# mouse_v1.net
KiCad netlist of a schematic drawn in EAGLE
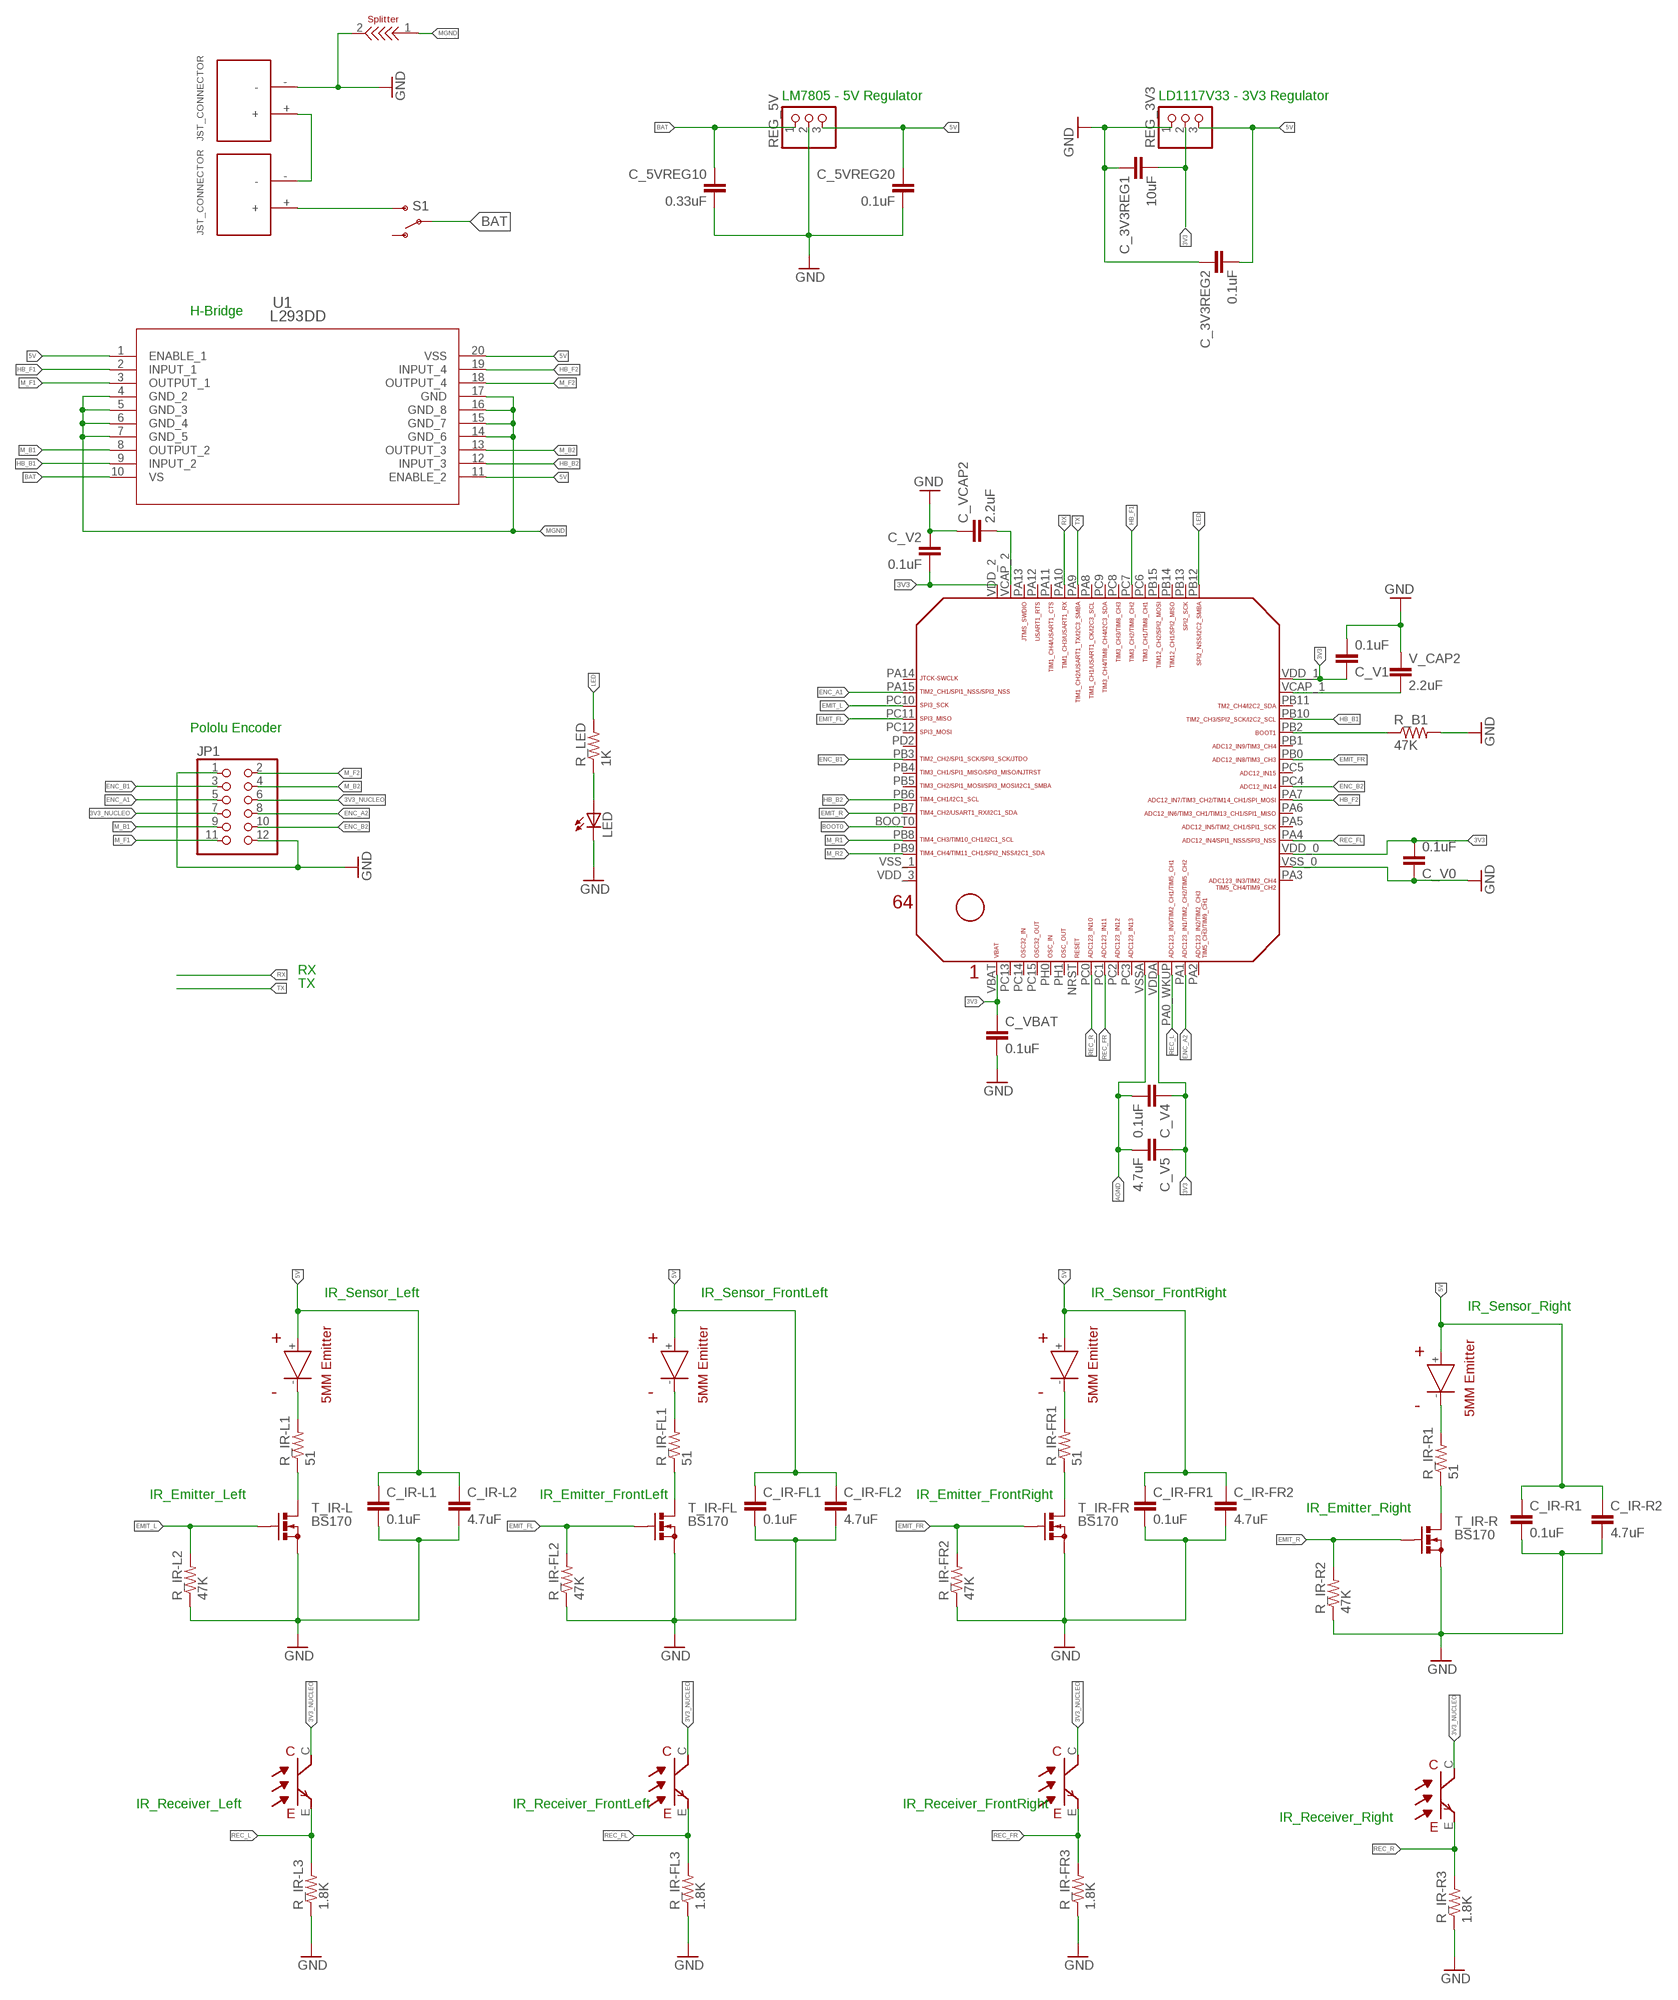
[diagram p0: schematic, sheet 1]

(export (version "E")
  (design (tool "Eeschema 10.0.6"))
  (components
    (comp (ref "C_3V3REG1")
      (value "10uF")
      (footprint "eagle-import:0603-CAP")
      (libsource (lib "eagle-import") (part "CAP0603-CAP"))
    )
    (comp (ref "C_3V3REG2")
      (value "0.1uF")
      (footprint "eagle-import:0603-CAP")
      (libsource (lib "eagle-import") (part "CAP0603-CAP"))
    )
    (comp (ref "C_5VREG10")
      (value "0.33uF")
      (footprint "eagle-import:0603-CAP")
      (libsource (lib "eagle-import") (part "CAP0603-CAP"))
    )
    (comp (ref "C_5VREG20")
      (value "0.1uF")
      (footprint "eagle-import:0603-CAP")
      (libsource (lib "eagle-import") (part "CAP0603-CAP"))
    )
    (comp (ref "C_IR-FL1")
      (value "0.1uF")
      (footprint "eagle-import:0603-CAP")
      (libsource (lib "eagle-import") (part "CAP0603-CAP"))
    )
    (comp (ref "C_IR-FL2")
      (value "4.7uF")
      (footprint "eagle-import:0603-CAP")
      (libsource (lib "eagle-import") (part "CAP0603-CAP"))
    )
    (comp (ref "C_IR-FR1")
      (value "0.1uF")
      (footprint "eagle-import:0603-CAP")
      (libsource (lib "eagle-import") (part "CAP0603-CAP"))
    )
    (comp (ref "C_IR-FR2")
      (value "4.7uF")
      (footprint "eagle-import:0603-CAP")
      (libsource (lib "eagle-import") (part "CAP0603-CAP"))
    )
    (comp (ref "C_IR-L1")
      (value "0.1uF")
      (footprint "eagle-import:0603-CAP")
      (libsource (lib "eagle-import") (part "CAP0603-CAP"))
    )
    (comp (ref "C_IR-L2")
      (value "4.7uF")
      (footprint "eagle-import:0603-CAP")
      (libsource (lib "eagle-import") (part "CAP0603-CAP"))
    )
    (comp (ref "C_IR-R1")
      (value "0.1uF")
      (footprint "eagle-import:0603-CAP")
      (libsource (lib "eagle-import") (part "CAP0603-CAP"))
    )
    (comp (ref "C_IR-R2")
      (value "4.7uF")
      (footprint "eagle-import:0603-CAP")
      (libsource (lib "eagle-import") (part "CAP0603-CAP"))
    )
    (comp (ref "C_V0")
      (value "0.1uF")
      (footprint "eagle-import:0603-CAP")
      (libsource (lib "eagle-import") (part "CAP0603-CAP"))
    )
    (comp (ref "C_V1")
      (value "0.1uF")
      (footprint "eagle-import:0603-CAP")
      (libsource (lib "eagle-import") (part "CAP0603-CAP"))
    )
    (comp (ref "C_V2")
      (value "0.1uF")
      (footprint "eagle-import:0603-CAP")
      (libsource (lib "eagle-import") (part "CAP0603-CAP"))
    )
    (comp (ref "C_V4")
      (value "0.1uF")
      (footprint "eagle-import:0603-CAP")
      (libsource (lib "eagle-import") (part "CAP0603-CAP"))
    )
    (comp (ref "C_V5")
      (value "4.7uF")
      (footprint "eagle-import:0603-CAP")
      (libsource (lib "eagle-import") (part "CAP0603-CAP"))
    )
    (comp (ref "C_VBAT")
      (value "0.1uF")
      (footprint "eagle-import:0603-CAP")
      (libsource (lib "eagle-import") (part "CAP0603-CAP"))
    )
    (comp (ref "C_VCAP2")
      (value "2.2uF")
      (footprint "eagle-import:0603-CAP")
      (libsource (lib "eagle-import") (part "CAP0603-CAP"))
    )
    (comp (ref "IR_FL")
      (value "EMITTER")
      (footprint "eagle-import:EMITTER")
      (libsource (lib "eagle-import") (part "EMITTER"))
    )
    (comp (ref "IR_FR")
      (value "EMITTER")
      (footprint "eagle-import:EMITTER")
      (libsource (lib "eagle-import") (part "EMITTER"))
    )
    (comp (ref "IR_L")
      (value "EMITTER")
      (footprint "eagle-import:EMITTER")
      (libsource (lib "eagle-import") (part "EMITTER"))
    )
    (comp (ref "IR_R")
      (value "EMITTER")
      (footprint "eagle-import:EMITTER")
      (libsource (lib "eagle-import") (part "EMITTER"))
    )
    (comp (ref "JP1")
      (value "PINHD-2X6")
      (footprint "eagle-import:2X06")
      (libsource (lib "eagle-import") (part "PINHD-2X6"))
    )
    (comp (ref "LED")
      (value "LEDCHIPLED_0603")
      (footprint "eagle-import:CHIPLED_0603")
      (libsource (lib "eagle-import") (part "LEDCHIPLED_0603"))
    )
    (comp (ref "REG_3V3")
      (value "PINHD-1X3")
      (footprint "eagle-import:1X03")
      (libsource (lib "eagle-import") (part "PINHD-1X3"))
    )
    (comp (ref "REG_5V")
      (value "PINHD-1X3")
      (footprint "eagle-import:1X03")
      (libsource (lib "eagle-import") (part "PINHD-1X3"))
    )
    (comp (ref "R_B1")
      (value "47K")
      (footprint "eagle-import:0603-RES")
      (libsource (lib "eagle-import") (part "1.8KOHM1/10W1%(0603)"))
    )
    (comp (ref "R_IR-FL1")
      (value "51")
      (footprint "eagle-import:0603-RES")
      (libsource (lib "eagle-import") (part "1.8KOHM1/10W1%(0603)"))
    )
    (comp (ref "R_IR-FL2")
      (value "47K")
      (footprint "eagle-import:0603-RES")
      (libsource (lib "eagle-import") (part "1.8KOHM1/10W1%(0603)"))
    )
    (comp (ref "R_IR-FL3")
      (value "1.8K")
      (footprint "eagle-import:0603-RES")
      (libsource (lib "eagle-import") (part "1.8KOHM1/10W1%(0603)"))
    )
    (comp (ref "R_IR-FR1")
      (value "51")
      (footprint "eagle-import:0603-RES")
      (libsource (lib "eagle-import") (part "1.8KOHM1/10W1%(0603)"))
    )
    (comp (ref "R_IR-FR2")
      (value "47K")
      (footprint "eagle-import:0603-RES")
      (libsource (lib "eagle-import") (part "1.8KOHM1/10W1%(0603)"))
    )
    (comp (ref "R_IR-FR3")
      (value "1.8K")
      (footprint "eagle-import:0603-RES")
      (libsource (lib "eagle-import") (part "1.8KOHM1/10W1%(0603)"))
    )
    (comp (ref "R_IR-L1")
      (value "51")
      (footprint "eagle-import:0603-RES")
      (libsource (lib "eagle-import") (part "1.8KOHM1/10W1%(0603)"))
    )
    (comp (ref "R_IR-L2")
      (value "47K")
      (footprint "eagle-import:0603-RES")
      (libsource (lib "eagle-import") (part "1.8KOHM1/10W1%(0603)"))
    )
    (comp (ref "R_IR-L3")
      (value "1.8K")
      (footprint "eagle-import:0603-RES")
      (libsource (lib "eagle-import") (part "1.8KOHM1/10W1%(0603)"))
    )
    (comp (ref "R_IR-R1")
      (value "51")
      (footprint "eagle-import:0603-RES")
      (libsource (lib "eagle-import") (part "1.8KOHM1/10W1%(0603)"))
    )
    (comp (ref "R_IR-R2")
      (value "47K")
      (footprint "eagle-import:0603-RES")
      (libsource (lib "eagle-import") (part "1.8KOHM1/10W1%(0603)"))
    )
    (comp (ref "R_IR-R3")
      (value "1.8K")
      (footprint "eagle-import:0603-RES")
      (libsource (lib "eagle-import") (part "1.8KOHM1/10W1%(0603)"))
    )
    (comp (ref "R_LED")
      (value "1K")
      (footprint "eagle-import:0603-RES")
      (libsource (lib "eagle-import") (part "1.8KOHM1/10W1%(0603)"))
    )
    (comp (ref "S1")
      (value "SWITCH-SPSTKIT")
      (footprint "eagle-import:SWITCH-SPDT_KIT")
      (libsource (lib "eagle-import") (part "SWITCH-SPSTKIT"))
    )
    (comp (ref "T_IR-FL")
      (value "BS170")
      (footprint "eagle-import:SOT54E")
      (libsource (lib "eagle-import") (part "BS170"))
    )
    (comp (ref "T_IR-FR")
      (value "BS170")
      (footprint "eagle-import:SOT54E")
      (libsource (lib "eagle-import") (part "BS170"))
    )
    (comp (ref "T_IR-L")
      (value "BS170")
      (footprint "eagle-import:SOT54E")
      (libsource (lib "eagle-import") (part "BS170"))
    )
    (comp (ref "T_IR-R")
      (value "BS170")
      (footprint "eagle-import:SOT54E")
      (libsource (lib "eagle-import") (part "BS170"))
    )
    (comp (ref "U$1")
      (value "STM32F405/415_LQFP64")
      (footprint "eagle-import:STM32F405_415_LQFP64")
      (libsource (lib "eagle-import") (part "STM32F405/415_LQFP64"))
    )
    (comp (ref "U$2")
      (value "JST_CONNECTOR_FEMALE")
      (footprint "eagle-import:JST_CONNECTOR_FEMALE")
      (libsource (lib "eagle-import") (part "JST_CONNECTOR_FEMALE"))
    )
    (comp (ref "U$3")
      (value "JST_CONNECTOR_FEMALE")
      (footprint "eagle-import:JST_CONNECTOR_FEMALE")
      (libsource (lib "eagle-import") (part "JST_CONNECTOR_FEMALE"))
    )
    (comp (ref "U$4")
      (value "RECEIVER")
      (footprint "eagle-import:RECEIVER")
      (libsource (lib "eagle-import") (part "RECEIVER"))
    )
    (comp (ref "U$5")
      (value "RECEIVER")
      (footprint "eagle-import:RECEIVER")
      (libsource (lib "eagle-import") (part "RECEIVER"))
    )
    (comp (ref "U$6")
      (value "RECEIVER")
      (footprint "eagle-import:RECEIVER")
      (libsource (lib "eagle-import") (part "RECEIVER"))
    )
    (comp (ref "U$7")
      (value "RECEIVER")
      (footprint "eagle-import:RECEIVER")
      (libsource (lib "eagle-import") (part "RECEIVER"))
    )
    (comp (ref "U$8")
      (value "SPLITTER")
      (footprint "eagle-import:SPLITTER")
      (libsource (lib "eagle-import") (part "SPLITTER"))
    )
    (comp (ref "U1")
      (value "L293DD")
      (footprint "eagle-import:SO-20")
      (libsource (lib "eagle-import") (part "L293DD"))
    )
    (comp (ref "V_CAP2")
      (value "2.2uF")
      (footprint "eagle-import:0603-CAP")
      (libsource (lib "eagle-import") (part "CAP0603-CAP"))
    )
  )
  (nets
    (net (code "1") (name "3V3") (class "Default")
      (node (ref "C_3V3REG1") (pin "2") (pinfunction "2_2") (pintype "passive"))
      (node (ref "C_V0") (pin "2") (pinfunction "2_2") (pintype "passive"))
      (node (ref "C_V1") (pin "1") (pinfunction "1_1") (pintype "passive"))
      (node (ref "C_V2") (pin "2") (pinfunction "2_2") (pintype "passive"))
      (node (ref "C_V4") (pin "1") (pinfunction "1_1") (pintype "passive"))
      (node (ref "C_V5") (pin "1") (pinfunction "1_1") (pintype "passive"))
      (node (ref "C_VBAT") (pin "1") (pinfunction "1_1") (pintype "passive"))
      (node (ref "REG_3V3") (pin "2") (pinfunction "2_2") (pintype "passive"))
      (node (ref "U$1") (pin "VBAT") (pinfunction "VBAT_VBAT") (pintype "bidirectional"))
      (node (ref "U$1") (pin "VDDA") (pinfunction "VDDA_VDDA") (pintype "bidirectional"))
      (node (ref "U$1") (pin "VDD_0") (pinfunction "VDD_0_VDD_0") (pintype "bidirectional"))
      (node (ref "U$1") (pin "VDD_1") (pinfunction "VDD_1_VDD_1") (pintype "bidirectional"))
      (node (ref "U$1") (pin "VDD_2") (pinfunction "VDD_2_VDD_2") (pintype "bidirectional"))
    )
    (net (code "2") (name "3V3_NUCLEO") (class "Default")
      (node (ref "JP1") (pin "6") (pinfunction "6_6") (pintype "passive"))
      (node (ref "JP1") (pin "7") (pinfunction "7_7") (pintype "passive"))
      (node (ref "U$4") (pin "C") (pinfunction "C_C") (pintype "bidirectional"))
      (node (ref "U$5") (pin "C") (pinfunction "C_C") (pintype "bidirectional"))
      (node (ref "U$6") (pin "C") (pinfunction "C_C") (pintype "bidirectional"))
      (node (ref "U$7") (pin "C") (pinfunction "C_C") (pintype "bidirectional"))
    )
    (net (code "3") (name "5V") (class "Default")
      (node (ref "C_3V3REG2") (pin "2") (pinfunction "2_2") (pintype "passive"))
      (node (ref "C_5VREG20") (pin "1") (pinfunction "1_1") (pintype "passive"))
      (node (ref "C_IR-FL1") (pin "1") (pinfunction "1_1") (pintype "passive"))
      (node (ref "C_IR-FL2") (pin "1") (pinfunction "1_1") (pintype "passive"))
      (node (ref "C_IR-FR1") (pin "1") (pinfunction "1_1") (pintype "passive"))
      (node (ref "C_IR-FR2") (pin "1") (pinfunction "1_1") (pintype "passive"))
      (node (ref "C_IR-L1") (pin "1") (pinfunction "1_1") (pintype "passive"))
      (node (ref "C_IR-L2") (pin "1") (pinfunction "1_1") (pintype "passive"))
      (node (ref "C_IR-R1") (pin "1") (pinfunction "1_1") (pintype "passive"))
      (node (ref "C_IR-R2") (pin "1") (pinfunction "1_1") (pintype "passive"))
      (node (ref "IR_FL") (pin "+") (pinfunction "+_+") (pintype "bidirectional"))
      (node (ref "IR_FR") (pin "+") (pinfunction "+_+") (pintype "bidirectional"))
      (node (ref "IR_L") (pin "+") (pinfunction "+_+") (pintype "bidirectional"))
      (node (ref "IR_R") (pin "+") (pinfunction "+_+") (pintype "bidirectional"))
      (node (ref "REG_3V3") (pin "3") (pinfunction "3_3") (pintype "passive"))
      (node (ref "REG_5V") (pin "3") (pinfunction "3_3") (pintype "passive"))
      (node (ref "U1") (pin "1") (pinfunction "ENABLE_1_1") (pintype "input"))
      (node (ref "U1") (pin "11") (pinfunction "ENABLE_2_11") (pintype "input"))
      (node (ref "U1") (pin "20") (pinfunction "VSS_20") (pintype "passive"))
    )
    (net (code "4") (name "AGND") (class "Default")
      (node (ref "C_V4") (pin "2") (pinfunction "2_2") (pintype "passive"))
      (node (ref "C_V5") (pin "2") (pinfunction "2_2") (pintype "passive"))
      (node (ref "U$1") (pin "VSSA") (pinfunction "VSSA_VSSA") (pintype "bidirectional"))
    )
    (net (code "5") (name "BAT") (class "Default")
      (node (ref "C_5VREG10") (pin "1") (pinfunction "1_1") (pintype "passive"))
      (node (ref "REG_5V") (pin "1") (pinfunction "1_1") (pintype "passive"))
      (node (ref "S1") (pin "2") (pinfunction "P_2") (pintype "passive"))
      (node (ref "U1") (pin "10") (pinfunction "VS_10") (pintype "passive"))
    )
    (net (code "6") (name "BOOT0") (class "Default")
      (node (ref "U$1") (pin "BOOT0") (pinfunction "BOOT0_BOOT0") (pintype "bidirectional"))
    )
    (net (code "7") (name "EMIT_FL") (class "Default")
      (node (ref "R_IR-FL2") (pin "2") (pinfunction "2_2") (pintype "passive"))
      (node (ref "T_IR-FL") (pin "G") (pinfunction "G_G") (pintype "passive"))
      (node (ref "U$1") (pin "PC11") (pinfunction "PC11_PC11") (pintype "bidirectional"))
    )
    (net (code "8") (name "EMIT_FR") (class "Default")
      (node (ref "R_IR-FR2") (pin "2") (pinfunction "2_2") (pintype "passive"))
      (node (ref "T_IR-FR") (pin "G") (pinfunction "G_G") (pintype "passive"))
      (node (ref "U$1") (pin "PB0") (pinfunction "PB0_PB0") (pintype "bidirectional"))
    )
    (net (code "9") (name "EMIT_L") (class "Default")
      (node (ref "R_IR-L2") (pin "2") (pinfunction "2_2") (pintype "passive"))
      (node (ref "T_IR-L") (pin "G") (pinfunction "G_G") (pintype "passive"))
      (node (ref "U$1") (pin "PC10") (pinfunction "PC10_PC10") (pintype "bidirectional"))
    )
    (net (code "10") (name "EMIT_R") (class "Default")
      (node (ref "R_IR-R2") (pin "2") (pinfunction "2_2") (pintype "passive"))
      (node (ref "T_IR-R") (pin "G") (pinfunction "G_G") (pintype "passive"))
      (node (ref "U$1") (pin "PB7") (pinfunction "PB7_PB7") (pintype "bidirectional"))
    )
    (net (code "11") (name "ENC_A1") (class "Default")
      (node (ref "JP1") (pin "5") (pinfunction "5_5") (pintype "passive"))
      (node (ref "U$1") (pin "PA15") (pinfunction "PA15_PA15") (pintype "bidirectional"))
    )
    (net (code "12") (name "ENC_A2") (class "Default")
      (node (ref "JP1") (pin "8") (pinfunction "8_8") (pintype "passive"))
      (node (ref "U$1") (pin "PA1") (pinfunction "PA1_PA1") (pintype "bidirectional"))
    )
    (net (code "13") (name "ENC_B1") (class "Default")
      (node (ref "JP1") (pin "3") (pinfunction "3_3") (pintype "passive"))
      (node (ref "U$1") (pin "PB3") (pinfunction "PB3_PB3") (pintype "bidirectional"))
    )
    (net (code "14") (name "ENC_B2") (class "Default")
      (node (ref "JP1") (pin "10") (pinfunction "10_10") (pintype "passive"))
      (node (ref "U$1") (pin "PC4") (pinfunction "PC4_PC4") (pintype "bidirectional"))
    )
    (net (code "15") (name "GND") (class "Default")
      (node (ref "C_3V3REG1") (pin "1") (pinfunction "1_1") (pintype "passive"))
      (node (ref "C_3V3REG2") (pin "1") (pinfunction "1_1") (pintype "passive"))
      (node (ref "C_5VREG10") (pin "2") (pinfunction "2_2") (pintype "passive"))
      (node (ref "C_5VREG20") (pin "2") (pinfunction "2_2") (pintype "passive"))
      (node (ref "C_IR-FL1") (pin "2") (pinfunction "2_2") (pintype "passive"))
      (node (ref "C_IR-FL2") (pin "2") (pinfunction "2_2") (pintype "passive"))
      (node (ref "C_IR-FR1") (pin "2") (pinfunction "2_2") (pintype "passive"))
      (node (ref "C_IR-FR2") (pin "2") (pinfunction "2_2") (pintype "passive"))
      (node (ref "C_IR-L1") (pin "2") (pinfunction "2_2") (pintype "passive"))
      (node (ref "C_IR-L2") (pin "2") (pinfunction "2_2") (pintype "passive"))
      (node (ref "C_IR-R1") (pin "2") (pinfunction "2_2") (pintype "passive"))
      (node (ref "C_IR-R2") (pin "2") (pinfunction "2_2") (pintype "passive"))
      (node (ref "C_V0") (pin "1") (pinfunction "1_1") (pintype "passive"))
      (node (ref "C_V1") (pin "2") (pinfunction "2_2") (pintype "passive"))
      (node (ref "C_V2") (pin "1") (pinfunction "1_1") (pintype "passive"))
      (node (ref "C_VBAT") (pin "2") (pinfunction "2_2") (pintype "passive"))
      (node (ref "C_VCAP2") (pin "1") (pinfunction "1_1") (pintype "passive"))
      (node (ref "JP1") (pin "1") (pinfunction "1_1") (pintype "passive"))
      (node (ref "JP1") (pin "12") (pinfunction "12_12") (pintype "passive"))
      (node (ref "LED") (pin "C") (pinfunction "C_C") (pintype "passive"))
      (node (ref "REG_3V3") (pin "1") (pinfunction "1_1") (pintype "passive"))
      (node (ref "REG_5V") (pin "2") (pinfunction "2_2") (pintype "passive"))
      (node (ref "R_B1") (pin "2") (pinfunction "2_2") (pintype "passive"))
      (node (ref "R_IR-FL2") (pin "1") (pinfunction "1_1") (pintype "passive"))
      (node (ref "R_IR-FL3") (pin "1") (pinfunction "1_1") (pintype "passive"))
      (node (ref "R_IR-FR2") (pin "1") (pinfunction "1_1") (pintype "passive"))
      (node (ref "R_IR-FR3") (pin "1") (pinfunction "1_1") (pintype "passive"))
      (node (ref "R_IR-L2") (pin "1") (pinfunction "1_1") (pintype "passive"))
      (node (ref "R_IR-L3") (pin "1") (pinfunction "1_1") (pintype "passive"))
      (node (ref "R_IR-R2") (pin "1") (pinfunction "1_1") (pintype "passive"))
      (node (ref "R_IR-R3") (pin "1") (pinfunction "1_1") (pintype "passive"))
      (node (ref "T_IR-FL") (pin "S") (pinfunction "S_S") (pintype "passive"))
      (node (ref "T_IR-FR") (pin "S") (pinfunction "S_S") (pintype "passive"))
      (node (ref "T_IR-L") (pin "S") (pinfunction "S_S") (pintype "passive"))
      (node (ref "T_IR-R") (pin "S") (pinfunction "S_S") (pintype "passive"))
      (node (ref "U$1") (pin "VSS_0") (pinfunction "VSS_0_VSS_0") (pintype "bidirectional"))
      (node (ref "U$2") (pin "-") (pinfunction "-_-") (pintype "bidirectional"))
      (node (ref "U$8") (pin "2") (pinfunction "2_2") (pintype "bidirectional"))
      (node (ref "V_CAP2") (pin "1") (pinfunction "1_1") (pintype "passive"))
    )
    (net (code "16") (name "HB_B1") (class "Default")
      (node (ref "U$1") (pin "PB10") (pinfunction "PB10_PB10") (pintype "bidirectional"))
      (node (ref "U1") (pin "9") (pinfunction "INPUT_2_9") (pintype "input"))
    )
    (net (code "17") (name "HB_B2") (class "Default")
      (node (ref "U$1") (pin "PB6") (pinfunction "PB6_PB6") (pintype "bidirectional"))
      (node (ref "U1") (pin "12") (pinfunction "INPUT_3_12") (pintype "input"))
    )
    (net (code "18") (name "HB_F1") (class "Default")
      (node (ref "U$1") (pin "PC7") (pinfunction "PC7_PC7") (pintype "bidirectional"))
      (node (ref "U1") (pin "2") (pinfunction "INPUT_1_2") (pintype "input"))
    )
    (net (code "19") (name "HB_F2") (class "Default")
      (node (ref "U$1") (pin "PA7") (pinfunction "PA7_PA7") (pintype "bidirectional"))
      (node (ref "U1") (pin "19") (pinfunction "INPUT_4_19") (pintype "input"))
    )
    (net (code "20") (name "LED") (class "Default")
      (node (ref "R_LED") (pin "2") (pinfunction "2_2") (pintype "passive"))
      (node (ref "U$1") (pin "PB12") (pinfunction "PB12_PB12") (pintype "bidirectional"))
    )
    (net (code "21") (name "MGND") (class "Default")
      (node (ref "U$8") (pin "1") (pinfunction "1_1") (pintype "bidirectional"))
      (node (ref "U1") (pin "14") (pinfunction "GND_6_14") (pintype "passive"))
      (node (ref "U1") (pin "15") (pinfunction "GND_7_15") (pintype "passive"))
      (node (ref "U1") (pin "16") (pinfunction "GND_8_16") (pintype "passive"))
      (node (ref "U1") (pin "17") (pinfunction "GND_17") (pintype "passive"))
      (node (ref "U1") (pin "4") (pinfunction "GND_2_4") (pintype "passive"))
      (node (ref "U1") (pin "5") (pinfunction "GND_3_5") (pintype "passive"))
      (node (ref "U1") (pin "6") (pinfunction "GND_4_6") (pintype "passive"))
      (node (ref "U1") (pin "7") (pinfunction "GND_5_7") (pintype "passive"))
    )
    (net (code "22") (name "M_B1") (class "Default")
      (node (ref "JP1") (pin "9") (pinfunction "9_9") (pintype "passive"))
      (node (ref "U1") (pin "8") (pinfunction "OUTPUT_2_8") (pintype "output"))
    )
    (net (code "23") (name "M_B2") (class "Default")
      (node (ref "JP1") (pin "4") (pinfunction "4_4") (pintype "passive"))
      (node (ref "U1") (pin "13") (pinfunction "OUTPUT_3_13") (pintype "output"))
    )
    (net (code "24") (name "M_F1") (class "Default")
      (node (ref "JP1") (pin "11") (pinfunction "11_11") (pintype "passive"))
      (node (ref "U1") (pin "3") (pinfunction "OUTPUT_1_3") (pintype "output"))
    )
    (net (code "25") (name "M_F2") (class "Default")
      (node (ref "JP1") (pin "2") (pinfunction "2_2") (pintype "passive"))
      (node (ref "U1") (pin "18") (pinfunction "OUTPUT_4_18") (pintype "output"))
    )
    (net (code "26") (name "M_R1") (class "Default")
      (node (ref "U$1") (pin "PB8") (pinfunction "PB8_PB8") (pintype "bidirectional"))
    )
    (net (code "27") (name "M_R2") (class "Default")
      (node (ref "U$1") (pin "PB9") (pinfunction "PB9_PB9") (pintype "bidirectional"))
    )
    (net (code "28") (name "Net-(C_VCAP2-Pad2)") (class "Default")
      (node (ref "C_VCAP2") (pin "2") (pinfunction "2_2") (pintype "passive"))
      (node (ref "U$1") (pin "VCAP_2") (pinfunction "VCAP_2_VCAP_2") (pintype "bidirectional"))
    )
    (net (code "29") (name "Net-(IR_FL-Pad-)") (class "Default")
      (node (ref "IR_FL") (pin "-") (pinfunction "-_-") (pintype "bidirectional"))
      (node (ref "R_IR-FL1") (pin "2") (pinfunction "2_2") (pintype "passive"))
    )
    (net (code "30") (name "Net-(IR_FR-Pad-)") (class "Default")
      (node (ref "IR_FR") (pin "-") (pinfunction "-_-") (pintype "bidirectional"))
      (node (ref "R_IR-FR1") (pin "2") (pinfunction "2_2") (pintype "passive"))
    )
    (net (code "31") (name "Net-(IR_L-Pad-)") (class "Default")
      (node (ref "IR_L") (pin "-") (pinfunction "-_-") (pintype "bidirectional"))
      (node (ref "R_IR-L1") (pin "2") (pinfunction "2_2") (pintype "passive"))
    )
    (net (code "32") (name "Net-(IR_R-Pad-)") (class "Default")
      (node (ref "IR_R") (pin "-") (pinfunction "-_-") (pintype "bidirectional"))
      (node (ref "R_IR-R1") (pin "2") (pinfunction "2_2") (pintype "passive"))
    )
    (net (code "33") (name "Net-(LED-PadA)") (class "Default")
      (node (ref "LED") (pin "A") (pinfunction "A_A") (pintype "passive"))
      (node (ref "R_LED") (pin "1") (pinfunction "1_1") (pintype "passive"))
    )
    (net (code "34") (name "Net-(R_B1-Pad1)") (class "Default")
      (node (ref "R_B1") (pin "1") (pinfunction "1_1") (pintype "passive"))
      (node (ref "U$1") (pin "PB2") (pinfunction "PB2_PB2") (pintype "bidirectional"))
    )
    (net (code "35") (name "Net-(R_IR-FL1-Pad1)") (class "Default")
      (node (ref "R_IR-FL1") (pin "1") (pinfunction "1_1") (pintype "passive"))
      (node (ref "T_IR-FL") (pin "D") (pinfunction "D_D") (pintype "passive"))
    )
    (net (code "36") (name "Net-(R_IR-FR1-Pad1)") (class "Default")
      (node (ref "R_IR-FR1") (pin "1") (pinfunction "1_1") (pintype "passive"))
      (node (ref "T_IR-FR") (pin "D") (pinfunction "D_D") (pintype "passive"))
    )
    (net (code "37") (name "Net-(R_IR-L1-Pad1)") (class "Default")
      (node (ref "R_IR-L1") (pin "1") (pinfunction "1_1") (pintype "passive"))
      (node (ref "T_IR-L") (pin "D") (pinfunction "D_D") (pintype "passive"))
    )
    (net (code "38") (name "Net-(R_IR-R1-Pad1)") (class "Default")
      (node (ref "R_IR-R1") (pin "1") (pinfunction "1_1") (pintype "passive"))
      (node (ref "T_IR-R") (pin "D") (pinfunction "D_D") (pintype "passive"))
    )
    (net (code "39") (name "Net-(S1-S)") (class "Default")
      (node (ref "S1") (pin "3") (pinfunction "S_3") (pintype "passive"))
      (node (ref "U$3") (pin "+") (pinfunction "+_+") (pintype "bidirectional"))
    )
    (net (code "40") (name "Net-(U$1-PadVCAP_1)") (class "Default")
      (node (ref "U$1") (pin "VCAP_1") (pinfunction "VCAP_1_VCAP_1") (pintype "bidirectional"))
      (node (ref "V_CAP2") (pin "2") (pinfunction "2_2") (pintype "passive"))
    )
    (net (code "41") (name "Net-(U$2-Pad+)") (class "Default")
      (node (ref "U$2") (pin "+") (pinfunction "+_+") (pintype "bidirectional"))
      (node (ref "U$3") (pin "-") (pinfunction "-_-") (pintype "bidirectional"))
    )
    (net (code "42") (name "REC_FL") (class "Default")
      (node (ref "R_IR-FL3") (pin "2") (pinfunction "2_2") (pintype "passive"))
      (node (ref "U$1") (pin "PA4") (pinfunction "PA4_PA4") (pintype "bidirectional"))
      (node (ref "U$5") (pin "E") (pinfunction "E_E") (pintype "bidirectional"))
    )
    (net (code "43") (name "REC_FR") (class "Default")
      (node (ref "R_IR-FR3") (pin "2") (pinfunction "2_2") (pintype "passive"))
      (node (ref "U$1") (pin "PC1") (pinfunction "PC1_PC1") (pintype "bidirectional"))
      (node (ref "U$6") (pin "E") (pinfunction "E_E") (pintype "bidirectional"))
    )
    (net (code "44") (name "REC_L") (class "Default")
      (node (ref "R_IR-L3") (pin "2") (pinfunction "2_2") (pintype "passive"))
      (node (ref "U$1") (pin "PA0_WKUP") (pinfunction "PA0_AKUP_PA0_WKUP") (pintype "bidirectional"))
      (node (ref "U$4") (pin "E") (pinfunction "E_E") (pintype "bidirectional"))
    )
    (net (code "45") (name "REC_R") (class "Default")
      (node (ref "R_IR-R3") (pin "2") (pinfunction "2_2") (pintype "passive"))
      (node (ref "U$1") (pin "PC0") (pinfunction "PC0_PC0") (pintype "bidirectional"))
      (node (ref "U$7") (pin "E") (pinfunction "E_E") (pintype "bidirectional"))
    )
    (net (code "46") (name "RX") (class "Default")
      (node (ref "U$1") (pin "PA10") (pinfunction "PA10_PA10") (pintype "bidirectional"))
    )
    (net (code "47") (name "TX") (class "Default")
      (node (ref "U$1") (pin "PA9") (pinfunction "PA9_PA9") (pintype "bidirectional"))
    )
    (net (code "48") (name "unconnected-(S1-O-Pad1)") (class "Default")
      (node (ref "S1") (pin "1") (pinfunction "O_1") (pintype "passive"))
    )
    (net (code "49") (name "unconnected-(U$1-PadNRST)") (class "Default")
      (node (ref "U$1") (pin "NRST") (pinfunction "NRST_NRST") (pintype "bidirectional"))
    )
    (net (code "50") (name "unconnected-(U$1-PadPA2)") (class "Default")
      (node (ref "U$1") (pin "PA2") (pinfunction "PA2_PA2") (pintype "bidirectional"))
    )
    (net (code "51") (name "unconnected-(U$1-PadPA3)") (class "Default")
      (node (ref "U$1") (pin "PA3") (pinfunction "PA3_PA3") (pintype "bidirectional"))
    )
    (net (code "52") (name "unconnected-(U$1-PadPA5)") (class "Default")
      (node (ref "U$1") (pin "PA5") (pinfunction "PA5_PA5") (pintype "bidirectional"))
    )
    (net (code "53") (name "unconnected-(U$1-PadPA6)") (class "Default")
      (node (ref "U$1") (pin "PA6") (pinfunction "PA6_PA6") (pintype "bidirectional"))
    )
    (net (code "54") (name "unconnected-(U$1-PadPA8)") (class "Default")
      (node (ref "U$1") (pin "PA8") (pinfunction "PA8_PA8") (pintype "bidirectional"))
    )
    (net (code "55") (name "unconnected-(U$1-PadPA11)") (class "Default")
      (node (ref "U$1") (pin "PA11") (pinfunction "PA11_PA11") (pintype "bidirectional"))
    )
    (net (code "56") (name "unconnected-(U$1-PadPA12)") (class "Default")
      (node (ref "U$1") (pin "PA12") (pinfunction "PA12_PA12") (pintype "bidirectional"))
    )
    (net (code "57") (name "unconnected-(U$1-PadPA13)") (class "Default")
      (node (ref "U$1") (pin "PA13") (pinfunction "PA13_PA13") (pintype "bidirectional"))
    )
    (net (code "58") (name "unconnected-(U$1-PadPA14)") (class "Default")
      (node (ref "U$1") (pin "PA14") (pinfunction "PA14_PA14") (pintype "bidirectional"))
    )
    (net (code "59") (name "unconnected-(U$1-PadPB1)") (class "Default")
      (node (ref "U$1") (pin "PB1") (pinfunction "PB1_PB1") (pintype "bidirectional"))
    )
    (net (code "60") (name "unconnected-(U$1-PadPB4)") (class "Default")
      (node (ref "U$1") (pin "PB4") (pinfunction "PB4_PB4") (pintype "bidirectional"))
    )
    (net (code "61") (name "unconnected-(U$1-PadPB5)") (class "Default")
      (node (ref "U$1") (pin "PB5") (pinfunction "PB5_PB5") (pintype "bidirectional"))
    )
    (net (code "62") (name "unconnected-(U$1-PadPB11)") (class "Default")
      (node (ref "U$1") (pin "PB11") (pinfunction "PB11_PB11") (pintype "bidirectional"))
    )
    (net (code "63") (name "unconnected-(U$1-PadPB13)") (class "Default")
      (node (ref "U$1") (pin "PB13") (pinfunction "PB13_PB13") (pintype "bidirectional"))
    )
    (net (code "64") (name "unconnected-(U$1-PadPB14)") (class "Default")
      (node (ref "U$1") (pin "PB14") (pinfunction "PB14_PB14") (pintype "bidirectional"))
    )
    (net (code "65") (name "unconnected-(U$1-PadPB15)") (class "Default")
      (node (ref "U$1") (pin "PB15") (pinfunction "PB15_PB15") (pintype "bidirectional"))
    )
    (net (code "66") (name "unconnected-(U$1-PadPC2)") (class "Default")
      (node (ref "U$1") (pin "PC2") (pinfunction "PC2_PC2") (pintype "bidirectional"))
    )
    (net (code "67") (name "unconnected-(U$1-PadPC3)") (class "Default")
      (node (ref "U$1") (pin "PC3") (pinfunction "PC3_PC3") (pintype "bidirectional"))
    )
    (net (code "68") (name "unconnected-(U$1-PadPC5)") (class "Default")
      (node (ref "U$1") (pin "PC5") (pinfunction "PC5_PC5") (pintype "bidirectional"))
    )
    (net (code "69") (name "unconnected-(U$1-PadPC6)") (class "Default")
      (node (ref "U$1") (pin "PC6") (pinfunction "PC6_PC6") (pintype "bidirectional"))
    )
    (net (code "70") (name "unconnected-(U$1-PadPC8)") (class "Default")
      (node (ref "U$1") (pin "PC8") (pinfunction "PC8_PC8") (pintype "bidirectional"))
    )
    (net (code "71") (name "unconnected-(U$1-PadPC9)") (class "Default")
      (node (ref "U$1") (pin "PC9") (pinfunction "PC9_PC9") (pintype "bidirectional"))
    )
    (net (code "72") (name "unconnected-(U$1-PadPC12)") (class "Default")
      (node (ref "U$1") (pin "PC12") (pinfunction "PC12_PC12") (pintype "bidirectional"))
    )
    (net (code "73") (name "unconnected-(U$1-PadPC13)") (class "Default")
      (node (ref "U$1") (pin "PC13") (pinfunction "PC13_PC13") (pintype "bidirectional"))
    )
    (net (code "74") (name "unconnected-(U$1-PadPC14)") (class "Default")
      (node (ref "U$1") (pin "PC14") (pinfunction "PC14_PC14") (pintype "bidirectional"))
    )
    (net (code "75") (name "unconnected-(U$1-PadPC15)") (class "Default")
      (node (ref "U$1") (pin "PC15") (pinfunction "PC15_PC15") (pintype "bidirectional"))
    )
    (net (code "76") (name "unconnected-(U$1-PadPD2)") (class "Default")
      (node (ref "U$1") (pin "PD2") (pinfunction "PD2_PD2") (pintype "bidirectional"))
    )
    (net (code "77") (name "unconnected-(U$1-PadPH0)") (class "Default")
      (node (ref "U$1") (pin "PH0") (pinfunction "PH0_PH0") (pintype "bidirectional"))
    )
    (net (code "78") (name "unconnected-(U$1-PadPH1)") (class "Default")
      (node (ref "U$1") (pin "PH1") (pinfunction "PH1_PH1") (pintype "bidirectional"))
    )
    (net (code "79") (name "unconnected-(U$1-PadVDD_3)") (class "Default")
      (node (ref "U$1") (pin "VDD_3") (pinfunction "VDD_3_VDD_3") (pintype "bidirectional"))
    )
    (net (code "80") (name "unconnected-(U$1-PadVSS_1)") (class "Default")
      (node (ref "U$1") (pin "VSS_1") (pinfunction "VSS_1_VSS_1") (pintype "bidirectional"))
    )
  )
)
